# 10AmpBuckV2.net
KiCad netlist of a schematic drawn in EAGLE
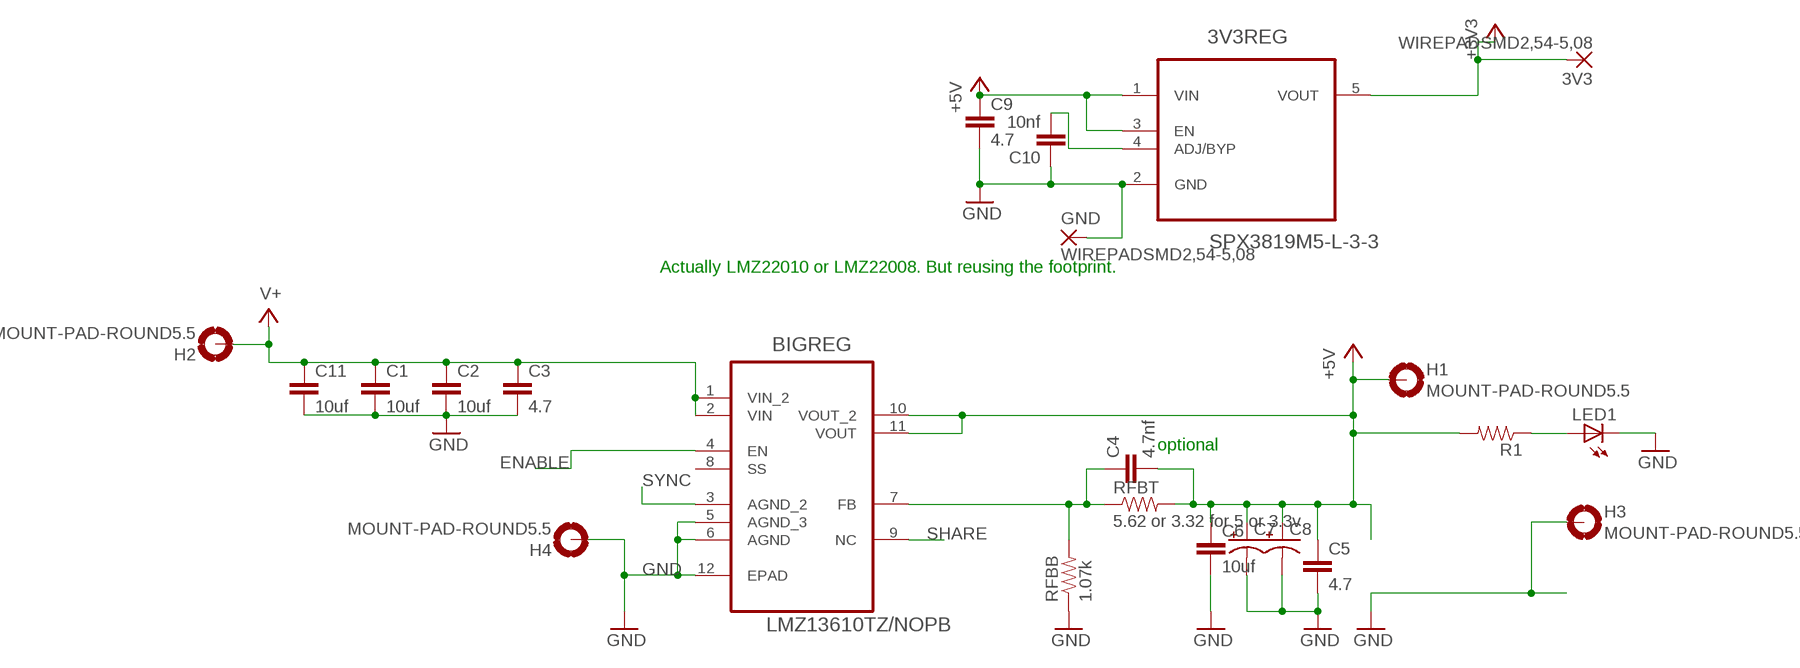
[diagram p0: schematic, sheet 1]

(export (version "E")
  (design (tool "Eeschema 10.0.6"))
  (components
    (comp (ref "3V3")
      (value "WIREPADSMD2,54-5,08")
      (footprint "eagle-import:SMD2,54-5,08")
      (libsource (lib "eagle-import") (part "WIREPADSMD2,54-5,08"))
    )
    (comp (ref "3V3REG")
      (value "SPX3819M5-L-3-3")
      (footprint "eagle-import:SOT95P280X145-5N")
      (libsource (lib "eagle-import") (part "SPX3819M5-L-3-3"))
    )
    (comp (ref "BIGREG")
      (value "LMZ13610TZ/NOPB")
      (footprint "eagle-import:TI_TO-PMOD-11")
      (libsource (lib "eagle-import") (part "LMZ13610TZ/NOPB"))
    )
    (comp (ref "C1")
      (value "10uf")
      (footprint "eagle-import:1206")
      (libsource (lib "eagle-import") (part "CAP1206"))
    )
    (comp (ref "C2")
      (value "10uf")
      (footprint "eagle-import:1206")
      (libsource (lib "eagle-import") (part "CAP1206"))
    )
    (comp (ref "C3")
      (value "4.7")
      (footprint "eagle-import:1206")
      (libsource (lib "eagle-import") (part "CAP1206"))
    )
    (comp (ref "C4")
      (value "4.7nf")
      (footprint "eagle-import:0603-CAP")
      (libsource (lib "eagle-import") (part "SparkFun-Passives_CAP0603-CAP"))
    )
    (comp (ref "C5")
      (value "4.7")
      (footprint "eagle-import:1206")
      (libsource (lib "eagle-import") (part "CAP1206"))
    )
    (comp (ref "C6")
      (value "10uf")
      (footprint "eagle-import:1206")
      (libsource (lib "eagle-import") (part "CAP1206"))
    )
    (comp (ref "C7")
      (value "CAP_POLPTH2")
      (footprint "eagle-import:CPOL-RADIAL-10UF-25V")
      (libsource (lib "eagle-import") (part "CAP_POLPTH2"))
    )
    (comp (ref "C8")
      (value "CAP_POLPTH2")
      (footprint "eagle-import:CPOL-RADIAL-10UF-25V")
      (libsource (lib "eagle-import") (part "CAP_POLPTH2"))
    )
    (comp (ref "C9")
      (value "4.7")
      (footprint "eagle-import:1206")
      (libsource (lib "eagle-import") (part "CAP1206"))
    )
    (comp (ref "C10")
      (value "10nf")
      (footprint "eagle-import:0603-CAP")
      (libsource (lib "eagle-import") (part "CAP0603-CAP"))
    )
    (comp (ref "C11")
      (value "10uf")
      (footprint "eagle-import:1206")
      (libsource (lib "eagle-import") (part "CAP1206"))
    )
    (comp (ref "GND")
      (value "WIREPADSMD2,54-5,08")
      (footprint "eagle-import:SMD2,54-5,08")
      (libsource (lib "eagle-import") (part "WIREPADSMD2,54-5,08"))
    )
    (comp (ref "H1")
      (value "MOUNT-PAD-ROUND5.5")
      (footprint "eagle-import:5,5-PAD")
      (libsource (lib "eagle-import") (part "MOUNT-PAD-ROUND5.5"))
    )
    (comp (ref "H2")
      (value "MOUNT-PAD-ROUND5.5")
      (footprint "eagle-import:5,5-PAD")
      (libsource (lib "eagle-import") (part "MOUNT-PAD-ROUND5.5"))
    )
    (comp (ref "H3")
      (value "MOUNT-PAD-ROUND5.5")
      (footprint "eagle-import:5,5-PAD")
      (libsource (lib "eagle-import") (part "MOUNT-PAD-ROUND5.5"))
    )
    (comp (ref "H4")
      (value "MOUNT-PAD-ROUND5.5")
      (footprint "eagle-import:5,5-PAD")
      (libsource (lib "eagle-import") (part "MOUNT-PAD-ROUND5.5"))
    )
    (comp (ref "LED1")
      (value "LED1206")
      (footprint "eagle-import:LED-1206")
      (libsource (lib "eagle-import") (part "LED1206"))
    )
    (comp (ref "R1")
      (value "RESISTOR0603-RES")
      (footprint "eagle-import:0603-RES")
      (libsource (lib "eagle-import") (part "RESISTOR0603-RES"))
    )
    (comp (ref "RFBB")
      (value "1.07k")
      (footprint "eagle-import:0603-RES")
      (libsource (lib "eagle-import") (part "RESISTOR0603"))
    )
    (comp (ref "RFBT")
      (value "5.62 or 3.32 for 5 or 3.3v")
      (footprint "eagle-import:0603-RES")
      (libsource (lib "eagle-import") (part "RESISTOR0603"))
    )
  )
  (nets
    (net (code "1") (name "+3V3") (class "Default")
      (node (ref "3V3") (pin "1") (pinfunction "P_1") (pintype "passive"))
      (node (ref "3V3REG") (pin "5") (pinfunction "VOUT_5") (pintype "output"))
    )
    (net (code "2") (name "+5V") (class "Default")
      (node (ref "3V3REG") (pin "1") (pinfunction "VIN_1") (pintype "power_in"))
      (node (ref "3V3REG") (pin "3") (pinfunction "EN_3") (pintype "input"))
      (node (ref "BIGREG") (pin "10") (pinfunction "VOUT_2_10") (pintype "output"))
      (node (ref "BIGREG") (pin "11") (pinfunction "VOUT_11") (pintype "output"))
      (node (ref "C4") (pin "2") (pinfunction "2_2") (pintype "passive"))
      (node (ref "C5") (pin "1") (pinfunction "1_1") (pintype "passive"))
      (node (ref "C6") (pin "1") (pinfunction "1_1") (pintype "passive"))
      (node (ref "C7") (pin "1") (pinfunction "+_1") (pintype "passive"))
      (node (ref "C8") (pin "1") (pinfunction "+_1") (pintype "passive"))
      (node (ref "C9") (pin "1") (pinfunction "1_1") (pintype "passive"))
      (node (ref "H1") (pin "B5,5") (pinfunction "MOUNT_B5,5") (pintype "passive"))
      (node (ref "R1") (pin "2") (pinfunction "2_2") (pintype "passive"))
      (node (ref "RFBT") (pin "2") (pinfunction "2_2") (pintype "passive"))
    )
    (net (code "3") (name "/ENABLE") (class "Default")
      (node (ref "BIGREG") (pin "4") (pinfunction "EN_4") (pintype "input"))
    )
    (net (code "5") (name "/SYNC") (class "Default")
      (node (ref "BIGREG") (pin "3") (pinfunction "AGND_2_3") (pintype "passive"))
    )
    (net (code "6") (name "GND") (class "Default")
      (node (ref "3V3REG") (pin "2") (pinfunction "GND_2") (pintype "passive"))
      (node (ref "BIGREG") (pin "12") (pinfunction "EPAD_12") (pintype "passive"))
      (node (ref "BIGREG") (pin "5") (pinfunction "AGND_3_5") (pintype "passive"))
      (node (ref "BIGREG") (pin "6") (pinfunction "AGND_6") (pintype "passive"))
      (node (ref "C1") (pin "2") (pinfunction "2_2") (pintype "passive"))
      (node (ref "C10") (pin "1") (pinfunction "1_1") (pintype "passive"))
      (node (ref "C11") (pin "2") (pinfunction "2_2") (pintype "passive"))
      (node (ref "C2") (pin "2") (pinfunction "2_2") (pintype "passive"))
      (node (ref "C3") (pin "2") (pinfunction "2_2") (pintype "passive"))
      (node (ref "C5") (pin "2") (pinfunction "2_2") (pintype "passive"))
      (node (ref "C6") (pin "2") (pinfunction "2_2") (pintype "passive"))
      (node (ref "C7") (pin "2") (pinfunction "-_2") (pintype "passive"))
      (node (ref "C8") (pin "2") (pinfunction "-_2") (pintype "passive"))
      (node (ref "C9") (pin "2") (pinfunction "2_2") (pintype "passive"))
      (node (ref "GND") (pin "1") (pinfunction "P_1") (pintype "passive"))
      (node (ref "H3") (pin "B5,5") (pinfunction "MOUNT_B5,5") (pintype "passive"))
      (node (ref "H4") (pin "B5,5") (pinfunction "MOUNT_B5,5") (pintype "passive"))
      (node (ref "LED1") (pin "C") (pinfunction "C_C") (pintype "passive"))
      (node (ref "RFBB") (pin "1") (pinfunction "1_1") (pintype "passive"))
    )
    (net (code "7") (name "Net-(3V3REG-ADJ{slash}BYP)") (class "Default")
      (node (ref "3V3REG") (pin "4") (pinfunction "ADJ/BYP_4") (pintype "passive"))
      (node (ref "C10") (pin "2") (pinfunction "2_2") (pintype "passive"))
    )
    (net (code "8") (name "Net-(BIGREG-FB)") (class "Default")
      (node (ref "BIGREG") (pin "7") (pinfunction "FB_7") (pintype "input"))
      (node (ref "C4") (pin "1") (pinfunction "1_1") (pintype "passive"))
      (node (ref "RFBB") (pin "2") (pinfunction "2_2") (pintype "passive"))
      (node (ref "RFBT") (pin "1") (pinfunction "1_1") (pintype "passive"))
    )
    (net (code "9") (name "Net-(LED1-PadA)") (class "Default")
      (node (ref "LED1") (pin "A") (pinfunction "A_A") (pintype "passive"))
      (node (ref "R1") (pin "1") (pinfunction "1_1") (pintype "passive"))
    )
    (net (code "10") (name "V+") (class "Default")
      (node (ref "BIGREG") (pin "1") (pinfunction "VIN_2_1") (pintype "power_in"))
      (node (ref "BIGREG") (pin "2") (pinfunction "VIN_2") (pintype "power_in"))
      (node (ref "C1") (pin "1") (pinfunction "1_1") (pintype "passive"))
      (node (ref "C11") (pin "1") (pinfunction "1_1") (pintype "passive"))
      (node (ref "C2") (pin "1") (pinfunction "1_1") (pintype "passive"))
      (node (ref "C3") (pin "1") (pinfunction "1_1") (pintype "passive"))
      (node (ref "H2") (pin "B5,5") (pinfunction "MOUNT_B5,5") (pintype "passive"))
    )
    (net (code "11") (name "unconnected-(BIGREG-NC-Pad9)") (class "Default")
      (node (ref "BIGREG") (pin "9") (pinfunction "NC_9") (pintype "no_connect"))
    )
    (net (code "12") (name "unconnected-(BIGREG-SS-Pad8)") (class "Default")
      (node (ref "BIGREG") (pin "8") (pinfunction "SS_8") (pintype "input"))
    )
  )
)
